# Arduino_Ibus.net
KiCad netlist of a schematic drawn in EAGLE
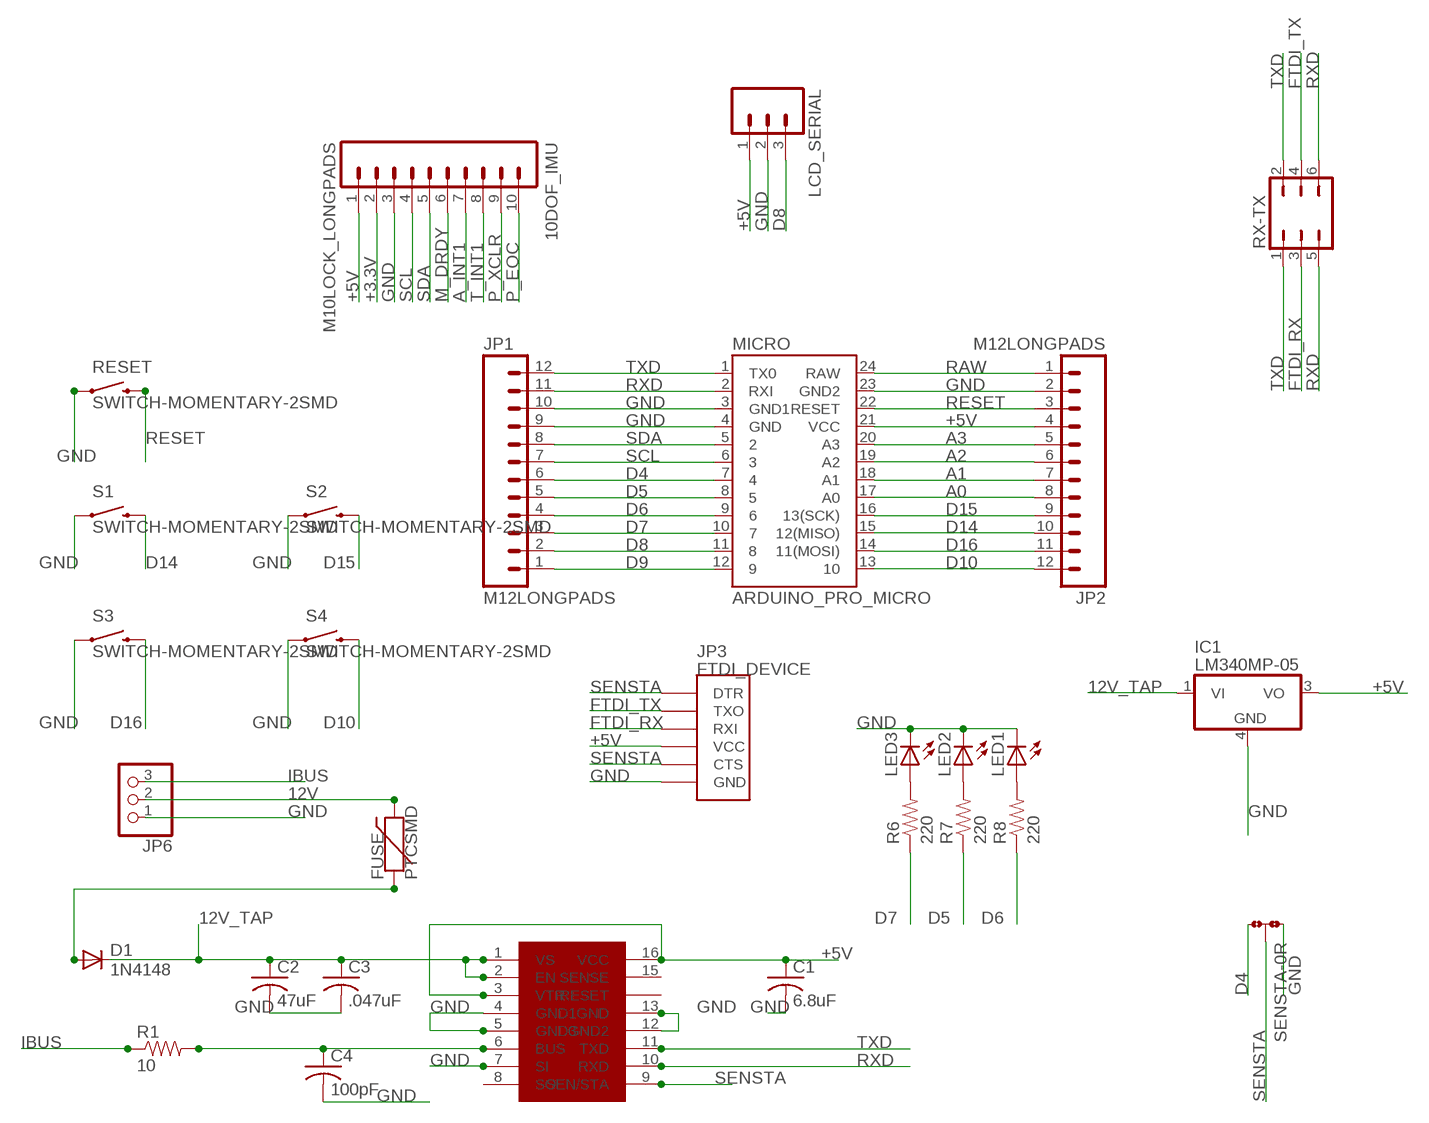
[diagram p0: schematic, sheet 1]

(export (version "E")
  (design (tool "Eeschema 10.0.6"))
  (components
    (comp (ref "10DOF_IMU")
      (value "M10LOCK_LONGPADS")
      (footprint "eagle-import:1X10_LOCK_LONGPADS")
      (libsource (lib "eagle-import") (part "M10LOCK_LONGPADS"))
    )
    (comp (ref "C1")
      (value "6.8uF")
      (footprint "eagle-import:C1206")
      (libsource (lib "eagle-import") (part "C-USC1206"))
    )
    (comp (ref "C2")
      (value "47uF")
      (footprint "eagle-import:C1206")
      (libsource (lib "eagle-import") (part "C-USC1206"))
    )
    (comp (ref "C3")
      (value ".047uF")
      (footprint "eagle-import:C1206")
      (libsource (lib "eagle-import") (part "C-USC1206"))
    )
    (comp (ref "C4")
      (value "100pF")
      (footprint "eagle-import:C1206")
      (libsource (lib "eagle-import") (part "C-USC1206"))
    )
    (comp (ref "D1")
      (value "1N4148")
      (footprint "eagle-import:SMA-DIODE")
      (libsource (lib "eagle-import") (part "DIODESMA"))
    )
    (comp (ref "FUSE")
      (value "PTCSMD")
      (footprint "eagle-import:PTC-1206")
      (libsource (lib "eagle-import") (part "PTCSMD"))
    )
    (comp (ref "IC1")
      (value "LM340MP-05")
      (footprint "eagle-import:SOT223")
      (libsource (lib "eagle-import") (part "LM340?-MP05"))
    )
    (comp (ref "JP1")
      (value "M12LONGPADS")
      (footprint "eagle-import:1X12_LONGPADS")
      (libsource (lib "eagle-import") (part "M12LONGPADS"))
    )
    (comp (ref "JP2")
      (value "M12LONGPADS")
      (footprint "eagle-import:1X12_LONGPADS")
      (libsource (lib "eagle-import") (part "M12LONGPADS"))
    )
    (comp (ref "JP3")
      (value "FTDI_DEVICE")
      (footprint "eagle-import:FTDI_DEVICE_SIDE")
      (libsource (lib "eagle-import") (part "FTDI_DEVICE"))
    )
    (comp (ref "JP6")
      (value "PINHD-1X3")
      (footprint "eagle-import:1X03")
      (libsource (lib "eagle-import") (part "PINHD-1X3"))
    )
    (comp (ref "LCD_SERIAL")
      (value "M03LOCK_LONGPADS")
      (footprint "eagle-import:1X03_LOCK_LONGPADS")
      (libsource (lib "eagle-import") (part "M03LOCK_LONGPADS"))
    )
    (comp (ref "LED1")
      (value "LED1206")
      (footprint "eagle-import:LED-1206")
      (libsource (lib "eagle-import") (part "LED1206"))
    )
    (comp (ref "LED2")
      (value "LED1206")
      (footprint "eagle-import:LED-1206")
      (libsource (lib "eagle-import") (part "LED1206"))
    )
    (comp (ref "LED3")
      (value "LED1206")
      (footprint "eagle-import:LED-1206")
      (libsource (lib "eagle-import") (part "LED1206"))
    )
    (comp (ref "MICRO")
      (value "ARDUINO_PRO_MICRO")
      (footprint "eagle-import:ARDUINO_PRO_MICRO")
      (libsource (lib "eagle-import") (part "ARDUINO_PRO_MICRO"))
    )
    (comp (ref "R1")
      (value "10")
      (footprint "eagle-import:1206")
      (libsource (lib "eagle-import") (part "RESISTOR1206"))
    )
    (comp (ref "R6")
      (value "220")
      (footprint "eagle-import:1206")
      (libsource (lib "eagle-import") (part "RESISTOR1206"))
    )
    (comp (ref "R7")
      (value "220")
      (footprint "eagle-import:1206")
      (libsource (lib "eagle-import") (part "RESISTOR1206"))
    )
    (comp (ref "R8")
      (value "220")
      (footprint "eagle-import:1206")
      (libsource (lib "eagle-import") (part "RESISTOR1206"))
    )
    (comp (ref "RESET")
      (value "SWITCH-MOMENTARY-2SMD")
      (footprint "eagle-import:TACTILE_SWITCH_SMD")
      (libsource (lib "eagle-import") (part "SWITCH-MOMENTARY-2SMD"))
    )
    (comp (ref "RX-TX")
      (value "JP3Q")
      (footprint "eagle-import:JP3Q")
      (libsource (lib "eagle-import") (part "JP3Q"))
    )
    (comp (ref "S1")
      (value "SWITCH-MOMENTARY-2SMD")
      (footprint "eagle-import:TACTILE_SWITCH_SMD")
      (libsource (lib "eagle-import") (part "SWITCH-MOMENTARY-2SMD"))
    )
    (comp (ref "S2")
      (value "SWITCH-MOMENTARY-2SMD")
      (footprint "eagle-import:TACTILE_SWITCH_SMD")
      (libsource (lib "eagle-import") (part "SWITCH-MOMENTARY-2SMD"))
    )
    (comp (ref "S3")
      (value "SWITCH-MOMENTARY-2SMD")
      (footprint "eagle-import:TACTILE_SWITCH_SMD")
      (libsource (lib "eagle-import") (part "SWITCH-MOMENTARY-2SMD"))
    )
    (comp (ref "S4")
      (value "SWITCH-MOMENTARY-2SMD")
      (footprint "eagle-import:TACTILE_SWITCH_SMD")
      (libsource (lib "eagle-import") (part "SWITCH-MOMENTARY-2SMD"))
    )
    (comp (ref "SENSTA")
      (value "0R-JUMPB")
      (footprint "eagle-import:B0R-JMP")
      (libsource (lib "eagle-import") (part "0R-JUMPB"))
    )
    (comp (ref "U$1")
      (value "TH3122")
      (footprint "eagle-import:SO16W")
      (libsource (lib "eagle-import") (part "TH3122"))
    )
  )
  (nets
    (net (code "1") (name "/+3.3V") (class "Default")
      (node (ref "10DOF_IMU") (pin "2") (pinfunction "2_2") (pintype "passive"))
    )
    (net (code "2") (name "/+5V") (class "Default")
      (node (ref "10DOF_IMU") (pin "1") (pinfunction "1_1") (pintype "passive"))
      (node (ref "C1") (pin "1") (pinfunction "1_1") (pintype "passive"))
      (node (ref "IC1") (pin "3") (pinfunction "VO_3") (pintype "passive"))
      (node (ref "JP2") (pin "4") (pinfunction "4_4") (pintype "passive"))
      (node (ref "JP3") (pin "P$4") (pinfunction "VCC_P$4") (pintype "bidirectional"))
      (node (ref "LCD_SERIAL") (pin "1") (pinfunction "1_1") (pintype "passive"))
      (node (ref "MICRO") (pin "21") (pinfunction "VCC_21") (pintype "bidirectional"))
      (node (ref "U$1") (pin "16") (pinfunction "VCC_16") (pintype "power_in"))
      (node (ref "U$1") (pin "3") (pinfunction "VTR_3") (pintype "bidirectional"))
    )
    (net (code "3") (name "/12V") (class "Default")
      (node (ref "FUSE") (pin "2") (pinfunction "2_2") (pintype "bidirectional"))
      (node (ref "JP6") (pin "2") (pinfunction "2_2") (pintype "passive"))
    )
    (net (code "4") (name "/12V_TAP") (class "Default")
      (node (ref "C2") (pin "1") (pinfunction "1_1") (pintype "passive"))
      (node (ref "C3") (pin "1") (pinfunction "1_1") (pintype "passive"))
      (node (ref "D1") (pin "C") (pinfunction "C_C") (pintype "passive"))
      (node (ref "IC1") (pin "1") (pinfunction "VI_1") (pintype "input"))
      (node (ref "U$1") (pin "1") (pinfunction "VS_1") (pintype "power_in"))
      (node (ref "U$1") (pin "2") (pinfunction "EN_2") (pintype "bidirectional"))
    )
    (net (code "5") (name "/A0") (class "Default")
      (node (ref "JP2") (pin "8") (pinfunction "8_8") (pintype "passive"))
      (node (ref "MICRO") (pin "17") (pinfunction "A0_17") (pintype "bidirectional"))
    )
    (net (code "6") (name "/A1") (class "Default")
      (node (ref "JP2") (pin "7") (pinfunction "7_7") (pintype "passive"))
      (node (ref "MICRO") (pin "18") (pinfunction "A1_18") (pintype "bidirectional"))
    )
    (net (code "7") (name "/A2") (class "Default")
      (node (ref "JP2") (pin "6") (pinfunction "6_6") (pintype "passive"))
      (node (ref "MICRO") (pin "19") (pinfunction "A2_19") (pintype "bidirectional"))
    )
    (net (code "8") (name "/A3") (class "Default")
      (node (ref "JP2") (pin "5") (pinfunction "5_5") (pintype "passive"))
      (node (ref "MICRO") (pin "20") (pinfunction "A3_20") (pintype "bidirectional"))
    )
    (net (code "9") (name "/A_INT1") (class "Default")
      (node (ref "10DOF_IMU") (pin "7") (pinfunction "7_7") (pintype "passive"))
    )
    (net (code "10") (name "/D4") (class "Default")
      (node (ref "JP1") (pin "6") (pinfunction "6_6") (pintype "passive"))
      (node (ref "MICRO") (pin "7") (pinfunction "4_7") (pintype "bidirectional"))
      (node (ref "SENSTA") (pin "3") (pinfunction "3_3") (pintype "passive"))
    )
    (net (code "11") (name "/D5") (class "Default")
      (node (ref "JP1") (pin "5") (pinfunction "5_5") (pintype "passive"))
      (node (ref "MICRO") (pin "8") (pinfunction "5_8") (pintype "bidirectional"))
      (node (ref "R7") (pin "1") (pinfunction "1_1") (pintype "passive"))
    )
    (net (code "12") (name "/D6") (class "Default")
      (node (ref "JP1") (pin "4") (pinfunction "4_4") (pintype "passive"))
      (node (ref "MICRO") (pin "9") (pinfunction "6_9") (pintype "bidirectional"))
      (node (ref "R8") (pin "1") (pinfunction "1_1") (pintype "passive"))
    )
    (net (code "13") (name "/D7") (class "Default")
      (node (ref "JP1") (pin "3") (pinfunction "3_3") (pintype "passive"))
      (node (ref "MICRO") (pin "10") (pinfunction "7_10") (pintype "bidirectional"))
      (node (ref "R6") (pin "1") (pinfunction "1_1") (pintype "passive"))
    )
    (net (code "14") (name "/D8") (class "Default")
      (node (ref "JP1") (pin "2") (pinfunction "2_2") (pintype "passive"))
      (node (ref "LCD_SERIAL") (pin "3") (pinfunction "3_3") (pintype "passive"))
      (node (ref "MICRO") (pin "11") (pinfunction "8_11") (pintype "bidirectional"))
    )
    (net (code "15") (name "/D9") (class "Default")
      (node (ref "JP1") (pin "1") (pinfunction "1_1") (pintype "passive"))
      (node (ref "MICRO") (pin "12") (pinfunction "9_12") (pintype "bidirectional"))
    )
    (net (code "16") (name "/D10") (class "Default")
      (node (ref "JP2") (pin "12") (pinfunction "12_12") (pintype "passive"))
      (node (ref "MICRO") (pin "13") (pinfunction "10_13") (pintype "bidirectional"))
      (node (ref "S4") (pin "3") (pinfunction "2_3") (pintype "passive"))
    )
    (net (code "17") (name "/D14") (class "Default")
      (node (ref "JP2") (pin "10") (pinfunction "10_10") (pintype "passive"))
      (node (ref "MICRO") (pin "15") (pinfunction "12(MISO)_15") (pintype "bidirectional"))
      (node (ref "S1") (pin "3") (pinfunction "2_3") (pintype "passive"))
    )
    (net (code "18") (name "/D15") (class "Default")
      (node (ref "JP2") (pin "9") (pinfunction "9_9") (pintype "passive"))
      (node (ref "MICRO") (pin "16") (pinfunction "13(SCK)_16") (pintype "bidirectional"))
      (node (ref "S2") (pin "3") (pinfunction "2_3") (pintype "passive"))
    )
    (net (code "19") (name "/D16") (class "Default")
      (node (ref "JP2") (pin "11") (pinfunction "11_11") (pintype "passive"))
      (node (ref "MICRO") (pin "14") (pinfunction "11(MOSI)_14") (pintype "bidirectional"))
      (node (ref "S3") (pin "3") (pinfunction "2_3") (pintype "passive"))
    )
    (net (code "20") (name "/FTDI_RX") (class "Default")
      (node (ref "JP3") (pin "P$3") (pinfunction "RXI_P$3") (pintype "bidirectional"))
      (node (ref "RX-TX") (pin "3") (pinfunction "3_3") (pintype "passive"))
    )
    (net (code "21") (name "/FTDI_TX") (class "Default")
      (node (ref "JP3") (pin "P$2") (pinfunction "TXO_P$2") (pintype "bidirectional"))
      (node (ref "RX-TX") (pin "4") (pinfunction "4_4") (pintype "passive"))
    )
    (net (code "22") (name "/GND") (class "Default")
      (node (ref "10DOF_IMU") (pin "3") (pinfunction "3_3") (pintype "passive"))
      (node (ref "C1") (pin "2") (pinfunction "2_2") (pintype "passive"))
      (node (ref "C2") (pin "2") (pinfunction "2_2") (pintype "passive"))
      (node (ref "C3") (pin "2") (pinfunction "2_2") (pintype "passive"))
      (node (ref "C4") (pin "2") (pinfunction "2_2") (pintype "passive"))
      (node (ref "IC1") (pin "4") (pinfunction "GND_4") (pintype "passive"))
      (node (ref "JP1") (pin "10") (pinfunction "10_10") (pintype "passive"))
      (node (ref "JP1") (pin "9") (pinfunction "9_9") (pintype "passive"))
      (node (ref "JP2") (pin "2") (pinfunction "2_2") (pintype "passive"))
      (node (ref "JP3") (pin "P$6") (pinfunction "GND_P$6") (pintype "bidirectional"))
      (node (ref "JP6") (pin "1") (pinfunction "1_1") (pintype "passive"))
      (node (ref "LCD_SERIAL") (pin "2") (pinfunction "2_2") (pintype "passive"))
      (node (ref "LED1") (pin "C") (pinfunction "C_C") (pintype "passive"))
      (node (ref "LED2") (pin "C") (pinfunction "C_C") (pintype "passive"))
      (node (ref "LED3") (pin "C") (pinfunction "C_C") (pintype "passive"))
      (node (ref "MICRO") (pin "23") (pinfunction "GND2_23") (pintype "bidirectional"))
      (node (ref "MICRO") (pin "3") (pinfunction "GND1_3") (pintype "bidirectional"))
      (node (ref "MICRO") (pin "4") (pinfunction "GND_4") (pintype "bidirectional"))
      (node (ref "RESET") (pin "1") (pinfunction "1_1") (pintype "passive"))
      (node (ref "S1") (pin "1") (pinfunction "1_1") (pintype "passive"))
      (node (ref "S2") (pin "1") (pinfunction "1_1") (pintype "passive"))
      (node (ref "S3") (pin "1") (pinfunction "1_1") (pintype "passive"))
      (node (ref "S4") (pin "1") (pinfunction "1_1") (pintype "passive"))
      (node (ref "SENSTA") (pin "1") (pinfunction "1_1") (pintype "passive"))
      (node (ref "U$1") (pin "12") (pinfunction "GND2_12") (pintype "power_in"))
      (node (ref "U$1") (pin "13") (pinfunction "GND_13") (pintype "power_in"))
      (node (ref "U$1") (pin "4") (pinfunction "GND1_4") (pintype "power_in"))
      (node (ref "U$1") (pin "5") (pinfunction "GND3_5") (pintype "power_in"))
      (node (ref "U$1") (pin "7") (pinfunction "SI_7") (pintype "bidirectional"))
    )
    (net (code "23") (name "/IBUS") (class "Default")
      (node (ref "JP6") (pin "3") (pinfunction "3_3") (pintype "passive"))
      (node (ref "R1") (pin "1") (pinfunction "1_1") (pintype "passive"))
    )
    (net (code "24") (name "/M_DRDY") (class "Default")
      (node (ref "10DOF_IMU") (pin "6") (pinfunction "6_6") (pintype "passive"))
    )
    (net (code "25") (name "/P_EOC") (class "Default")
      (node (ref "10DOF_IMU") (pin "10") (pinfunction "10_10") (pintype "passive"))
    )
    (net (code "26") (name "/P_XCLR") (class "Default")
      (node (ref "10DOF_IMU") (pin "9") (pinfunction "9_9") (pintype "passive"))
    )
    (net (code "27") (name "/RAW") (class "Default")
      (node (ref "JP2") (pin "1") (pinfunction "1_1") (pintype "passive"))
      (node (ref "MICRO") (pin "24") (pinfunction "RAW_24") (pintype "bidirectional"))
    )
    (net (code "28") (name "/RESET") (class "Default")
      (node (ref "JP2") (pin "3") (pinfunction "3_3") (pintype "passive"))
      (node (ref "MICRO") (pin "22") (pinfunction "RESET_22") (pintype "bidirectional"))
      (node (ref "RESET") (pin "3") (pinfunction "2_3") (pintype "passive"))
    )
    (net (code "29") (name "/RXD") (class "Default")
      (node (ref "JP1") (pin "11") (pinfunction "11_11") (pintype "passive"))
      (node (ref "MICRO") (pin "2") (pinfunction "RXI_2") (pintype "bidirectional"))
      (node (ref "RX-TX") (pin "5") (pinfunction "5_5") (pintype "passive"))
      (node (ref "RX-TX") (pin "6") (pinfunction "6_6") (pintype "passive"))
      (node (ref "U$1") (pin "10") (pinfunction "RXD_10") (pintype "input"))
    )
    (net (code "30") (name "/SCL") (class "Default")
      (node (ref "10DOF_IMU") (pin "4") (pinfunction "4_4") (pintype "passive"))
      (node (ref "JP1") (pin "7") (pinfunction "7_7") (pintype "passive"))
      (node (ref "MICRO") (pin "6") (pinfunction "3_6") (pintype "bidirectional"))
    )
    (net (code "31") (name "/SDA") (class "Default")
      (node (ref "10DOF_IMU") (pin "5") (pinfunction "5_5") (pintype "passive"))
      (node (ref "JP1") (pin "8") (pinfunction "8_8") (pintype "passive"))
      (node (ref "MICRO") (pin "5") (pinfunction "2_5") (pintype "bidirectional"))
    )
    (net (code "32") (name "/SENSTA") (class "Default")
      (node (ref "JP3") (pin "P$1") (pinfunction "DTR_P$1") (pintype "bidirectional"))
      (node (ref "JP3") (pin "P$5") (pinfunction "CTS_P$5") (pintype "bidirectional"))
      (node (ref "SENSTA") (pin "2") (pinfunction "2_2") (pintype "passive"))
      (node (ref "U$1") (pin "9") (pinfunction "SEN/STA_9") (pintype "bidirectional"))
    )
    (net (code "33") (name "/TXD") (class "Default")
      (node (ref "JP1") (pin "12") (pinfunction "12_12") (pintype "passive"))
      (node (ref "MICRO") (pin "1") (pinfunction "TX0_1") (pintype "bidirectional"))
      (node (ref "RX-TX") (pin "1") (pinfunction "1_1") (pintype "passive"))
      (node (ref "RX-TX") (pin "2") (pinfunction "2_2") (pintype "passive"))
      (node (ref "U$1") (pin "11") (pinfunction "TXD_11") (pintype "output"))
    )
    (net (code "34") (name "/T_INT1") (class "Default")
      (node (ref "10DOF_IMU") (pin "8") (pinfunction "8_8") (pintype "passive"))
    )
    (net (code "35") (name "Net-(D1-PadA)") (class "Default")
      (node (ref "D1") (pin "A") (pinfunction "A_A") (pintype "passive"))
      (node (ref "FUSE") (pin "1") (pinfunction "1_1") (pintype "bidirectional"))
    )
    (net (code "36") (name "Net-(LED1-PadA)") (class "Default")
      (node (ref "LED1") (pin "A") (pinfunction "A_A") (pintype "passive"))
      (node (ref "R8") (pin "2") (pinfunction "2_2") (pintype "passive"))
    )
    (net (code "37") (name "Net-(LED2-PadA)") (class "Default")
      (node (ref "LED2") (pin "A") (pinfunction "A_A") (pintype "passive"))
      (node (ref "R7") (pin "2") (pinfunction "2_2") (pintype "passive"))
    )
    (net (code "38") (name "Net-(LED3-PadA)") (class "Default")
      (node (ref "LED3") (pin "A") (pinfunction "A_A") (pintype "passive"))
      (node (ref "R6") (pin "2") (pinfunction "2_2") (pintype "passive"))
    )
    (net (code "39") (name "Net-(U$1-BUS)") (class "Default")
      (node (ref "C4") (pin "1") (pinfunction "1_1") (pintype "passive"))
      (node (ref "R1") (pin "2") (pinfunction "2_2") (pintype "passive"))
      (node (ref "U$1") (pin "6") (pinfunction "BUS_6") (pintype "bidirectional"))
    )
    (net (code "40") (name "unconnected-(U$1-RESET-Pad14)") (class "Default")
      (node (ref "U$1") (pin "14") (pinfunction "RESET_14") (pintype "bidirectional"))
    )
    (net (code "41") (name "unconnected-(U$1-SENSE-Pad15)") (class "Default")
      (node (ref "U$1") (pin "15") (pinfunction "SENSE_15") (pintype "bidirectional"))
    )
    (net (code "42") (name "unconnected-(U$1-SO-Pad8)") (class "Default")
      (node (ref "U$1") (pin "8") (pinfunction "SO_8") (pintype "bidirectional"))
    )
  )
)
